# analog_channel_ABS_AMP.net
KiCad netlist of a schematic drawn in Altium Designer
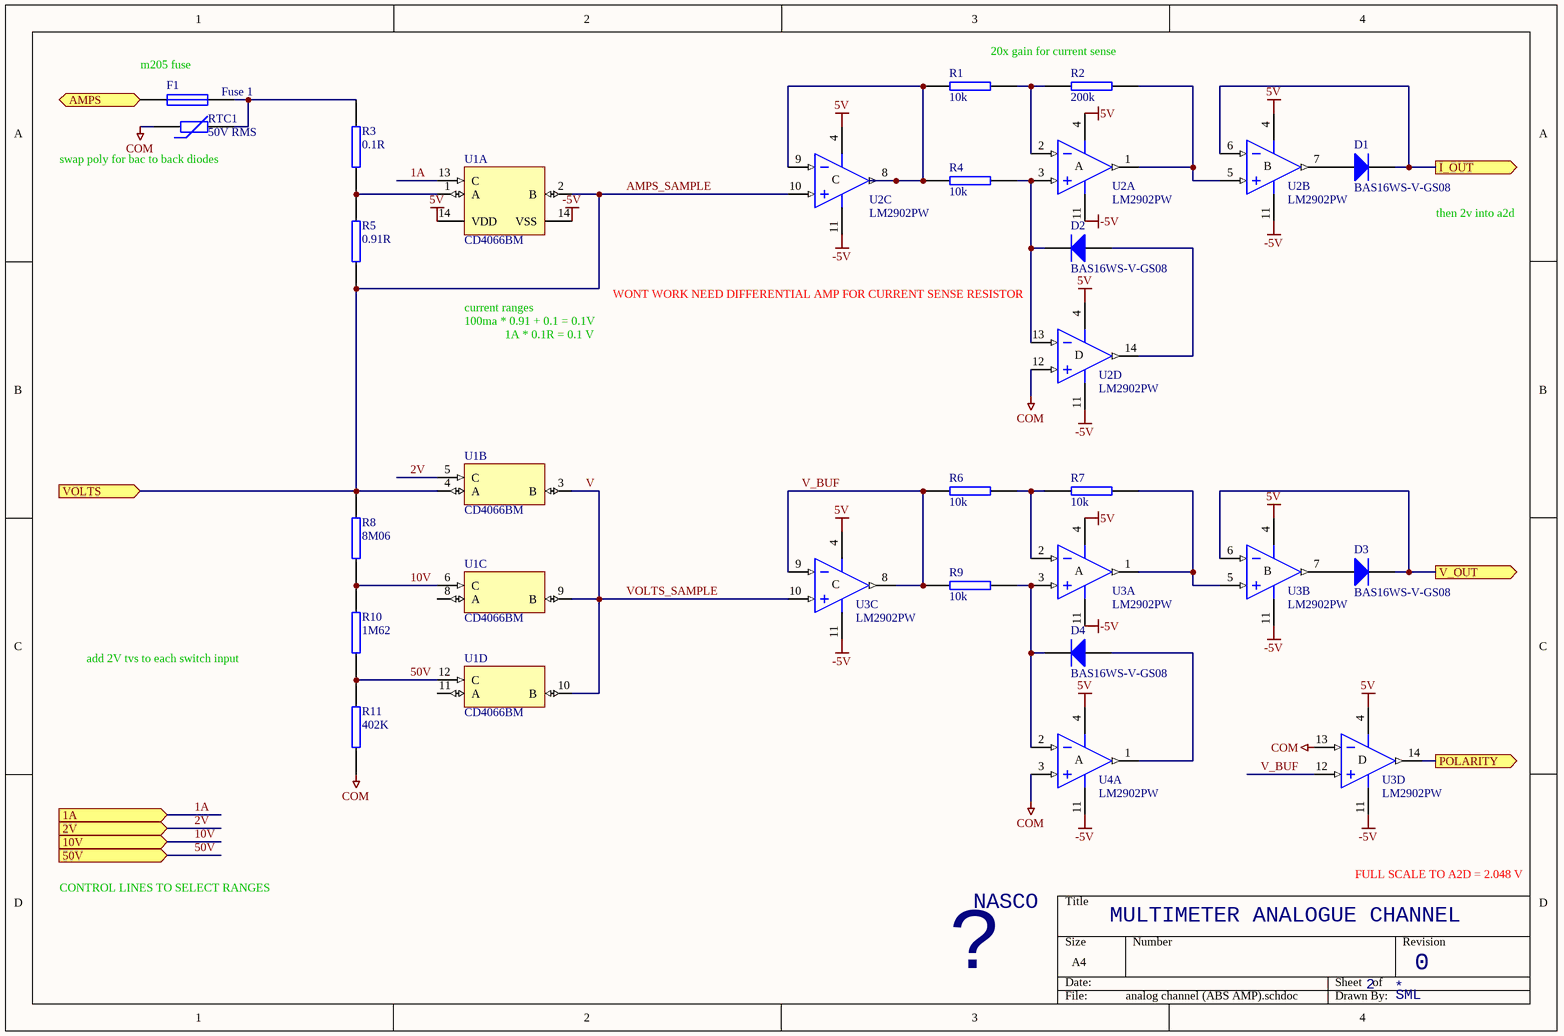
[diagram p0: analog channel (ABS AMP).schdoc]

(export (version "E")
  (design (tool "Eeschema 10.0.6"))
  (components
    (comp (ref "D1")
      (value "BAS16WS-V-GS08")
      (footprint "SMC")
      (description "Default Diode")
      (libsource (lib "Miscellaneous Devices") (part "Diode"))
    )
    (comp (ref "D2")
      (value "BAS16WS-V-GS08")
      (footprint "SMC")
      (description "Default Diode")
      (libsource (lib "Miscellaneous Devices") (part "Diode"))
    )
    (comp (ref "D3")
      (value "BAS16WS-V-GS08")
      (footprint "SMC")
      (description "Default Diode")
      (libsource (lib "Miscellaneous Devices") (part "Diode"))
    )
    (comp (ref "D4")
      (value "BAS16WS-V-GS08")
      (footprint "SMC")
      (description "Default Diode")
      (libsource (lib "Miscellaneous Devices") (part "Diode"))
    )
    (comp (ref "F1")
      (value "Fuse 1")
      (footprint "PIN-W2/E2.8")
      (description "Fuse")
      (libsource (lib "Miscellaneous Devices") (part "Fuse 1"))
    )
    (comp (ref "R1")
      (value "10k")
      (footprint "RES(3D) - 0603")
      (description "RESISTOR SMD 0603 10k")
      (fields (field (name "MOUSER PART NO.") "652-CR0603FX-1002ELF") (field (name "MANUFACTURER") "Bourns"))
      (libsource (lib "NASCO Resistors") (part "RES SMD 0603 10k"))
    )
    (comp (ref "R2")
      (value "200k")
      (footprint "RES(3D) - 0603")
      (description "RESISTOR SMD 0603 10k")
      (fields (field (name "MOUSER PART NO.") "652-CR0603FX-1002ELF") (field (name "MANUFACTURER") "Bourns"))
      (libsource (lib "NASCO Resistors") (part "RES SMD 0603 10k"))
    )
    (comp (ref "R3")
      (value "0.1R")
      (footprint "RES (3D) - 0805")
      (description "RESISTOR SMD 0603 10k")
      (fields (field (name "MOUSER PART NO.") "652-CRL0805JWR100ELF") (field (name "MANUFACTURER") "Bourns"))
      (libsource (lib "NASCO Resistors") (part "RES SMD 0603 10k"))
    )
    (comp (ref "R4")
      (value "10k")
      (footprint "RES(3D) - 0603")
      (description "RESISTOR SMD 0603 10k")
      (fields (field (name "MOUSER PART NO.") "652-CR0603FX-1002ELF") (field (name "MANUFACTURER") "Bourns"))
      (libsource (lib "NASCO Resistors") (part "RES SMD 0603 10k"))
    )
    (comp (ref "R5")
      (value "0.91R")
      (footprint "RES (3D) - 0805")
      (description "RESISTOR SMD 0603 10k")
      (fields (field (name "MOUSER PART NO.") "774-73L3R91J") (field (name "MANUFACTURER") "Bourns"))
      (libsource (lib "NASCO Resistors") (part "RES SMD 0603 10k"))
    )
    (comp (ref "R6")
      (value "10k")
      (footprint "RES(3D) - 0603")
      (description "RESISTOR SMD 0603 10k")
      (fields (field (name "MOUSER PART NO.") "652-CR0603FX-1002ELF") (field (name "MANUFACTURER") "Bourns"))
      (libsource (lib "NASCO Resistors") (part "RES SMD 0603 10k"))
    )
    (comp (ref "R7")
      (value "10k")
      (footprint "RES(3D) - 0603")
      (description "RESISTOR SMD 0603 10k")
      (fields (field (name "MOUSER PART NO.") "652-CR0603FX-1002ELF") (field (name "MANUFACTURER") "Bourns"))
      (libsource (lib "NASCO Resistors") (part "RES SMD 0603 10k"))
    )
    (comp (ref "R8")
      (value "8M06")
      (footprint "RES(3D) - 0603")
      (description "RESISTOR SMD 0603 10k")
      (fields
        (field (name "MOUSER PART NO.") "71-CRCW0603-8.06M-E3")
        (field (name "MANUFACTURER") "Vishay/Dale")
      )
      (libsource (lib "NASCO Resistors") (part "RES SMD 0603 10k"))
    )
    (comp (ref "R9")
      (value "10k")
      (footprint "RES(3D) - 0603")
      (description "RESISTOR SMD 0603 10k")
      (fields (field (name "MOUSER PART NO.") "652-CR0603FX-1002ELF") (field (name "MANUFACTURER") "Bourns"))
      (libsource (lib "NASCO Resistors") (part "RES SMD 0603 10k"))
    )
    (comp (ref "R10")
      (value "1M62")
      (footprint "RES(3D) - 0603")
      (description "RESISTOR SMD 0603 10k")
      (fields
        (field (name "MOUSER PART NO.") "Vishay/Dale")
        (field (name "MANUFACTURER") "71-CRCW0603-1.62M-E3")
      )
      (libsource (lib "NASCO Resistors") (part "RES SMD 0603 10k"))
    )
    (comp (ref "R11")
      (value "402K")
      (footprint "RES(3D) - 0603")
      (description "RESISTOR SMD 0603 10k")
      (fields (field (name "MOUSER PART NO.") "652-CR0603FX-4023ELF") (field (name "MANUFACTURER") "Bourns"))
      (libsource (lib "NASCO Resistors") (part "RES SMD 0603 10k"))
    )
    (comp (ref "RTC1")
      (value "50V RMS")
      (footprint "6-0805_N")
      (description "Varistor (Voltage-Sensitive Resistor)")
      (fields (field (name "MANUFACTURER") "Bourns") (field (name "MANUFACTURER PART NO.") "MOV-07D820K"))
      (libsource (lib "Miscellaneous Devices") (part "Res Varistor"))
    )
    (comp (ref "U1")
      (value "CD4066BM")
      (footprint "D014_N")
      (description "Quadruple Bilateral Analog Switch")
      (fields (field (name "MOUSER PART NUMBER") "595-CD4066BM"))
      (libsource (lib "Schlib1") (part "CD4066"))
    )
    (comp (ref "U2")
      (value "LM2902PW")
      (footprint "PW014_N")
      (description "Quadruple Operational Amplifier")
      (libsource (lib "TI Operational Amplifier") (part "LM2902PW"))
    )
    (comp (ref "U3")
      (value "LM2902PW")
      (footprint "PW014_N")
      (description "Quadruple Operational Amplifier")
      (libsource (lib "TI Operational Amplifier") (part "LM2902PW"))
    )
    (comp (ref "U4")
      (value "LM2902PW")
      (footprint "PW014_N")
      (description "Quadruple Operational Amplifier")
      (libsource (lib "TI Operational Amplifier") (part "LM2902PW"))
    )
  )
  (nets
    (net (code "1") (name "-5V") (class "Default")
      (node (ref "U1") (pin "14") (pinfunction "VSS_14") (pintype "passive"))
      (node (ref "U2") (pin "11") (pinfunction "V-_11") (pintype "power_in"))
      (node (ref "U3") (pin "11") (pinfunction "V-_11") (pintype "power_in"))
      (node (ref "U4") (pin "11") (pinfunction "V-_11") (pintype "power_in"))
    )
    (net (code "2") (name "/1A") (class "Default")
      (node (ref "U1") (pin "13") (pinfunction "C_13") (pintype "input"))
    )
    (net (code "3") (name "/2V") (class "Default")
      (node (ref "U1") (pin "5") (pinfunction "C_5") (pintype "input"))
    )
    (net (code "4") (name "/10V") (class "Default")
      (node (ref "R10") (pin "1") (pinfunction "1_1") (pintype "passive"))
      (node (ref "R8") (pin "2") (pinfunction "2_2") (pintype "passive"))
      (node (ref "U1") (pin "6") (pinfunction "C_6") (pintype "input"))
    )
    (net (code "5") (name "/50V") (class "Default")
      (node (ref "R10") (pin "2") (pinfunction "2_2") (pintype "passive"))
      (node (ref "R11") (pin "1") (pinfunction "1_1") (pintype "passive"))
      (node (ref "U1") (pin "12") (pinfunction "C_12") (pintype "input"))
    )
    (net (code "6") (name "/AMPS") (class "Default")
      (node (ref "F1") (pin "1") (pinfunction "1_1") (pintype "passive"))
    )
    (net (code "7") (name "/AMPS_SAMPLE") (class "Default")
      (node (ref "R5") (pin "2") (pinfunction "2_2") (pintype "passive"))
      (node (ref "R8") (pin "1") (pinfunction "1_1") (pintype "passive"))
      (node (ref "U1") (pin "2") (pinfunction "B_2") (pintype "bidirectional"))
      (node (ref "U1") (pin "4") (pinfunction "A_4") (pintype "bidirectional"))
      (node (ref "U2") (pin "10") (pinfunction "IN+_10") (pintype "input"))
    )
    (net (code "8") (name "/I_OUT") (class "Default")
      (node (ref "D1") (pin "2") (pinfunction "K_2") (pintype "passive"))
      (node (ref "U2") (pin "6") (pinfunction "IN-_6") (pintype "input"))
    )
    (net (code "9") (name "/POLARITY") (class "Default")
      (node (ref "U3") (pin "14") (pinfunction "OUT_14") (pintype "output"))
    )
    (net (code "10") (name "/V") (class "Default")
      (node (ref "U1") (pin "10") (pinfunction "B_10") (pintype "bidirectional"))
      (node (ref "U1") (pin "3") (pinfunction "B_3") (pintype "bidirectional"))
      (node (ref "U1") (pin "9") (pinfunction "B_9") (pintype "bidirectional"))
      (node (ref "U3") (pin "10") (pinfunction "IN+_10") (pintype "input"))
    )
    (net (code "11") (name "/V_BUF") (class "Default")
      (node (ref "R6") (pin "1") (pinfunction "1_1") (pintype "passive"))
      (node (ref "R9") (pin "1") (pinfunction "1_1") (pintype "passive"))
      (node (ref "U3") (pin "12") (pinfunction "IN+_12") (pintype "input"))
      (node (ref "U3") (pin "8") (pinfunction "OUT_8") (pintype "output"))
      (node (ref "U3") (pin "9") (pinfunction "IN-_9") (pintype "input"))
    )
    (net (code "12") (name "/V_OUT") (class "Default")
      (node (ref "D3") (pin "2") (pinfunction "K_2") (pintype "passive"))
      (node (ref "U3") (pin "6") (pinfunction "IN-_6") (pintype "input"))
    )
    (net (code "13") (name "5V") (class "Default")
      (node (ref "U1") (pin "14") (pinfunction "VDD_14") (pintype "passive"))
      (node (ref "U2") (pin "4") (pinfunction "V+_4") (pintype "power_in"))
      (node (ref "U3") (pin "4") (pinfunction "V+_4") (pintype "power_in"))
      (node (ref "U4") (pin "4") (pinfunction "V+_4") (pintype "power_in"))
    )
    (net (code "14") (name "COM") (class "Default")
      (node (ref "R11") (pin "2") (pinfunction "2_2") (pintype "passive"))
      (node (ref "RTC1") (pin "1") (pinfunction "1_1") (pintype "passive"))
      (node (ref "U2") (pin "12") (pinfunction "IN+_12") (pintype "input"))
      (node (ref "U3") (pin "13") (pinfunction "IN-_13") (pintype "input"))
      (node (ref "U4") (pin "3") (pinfunction "IN+_3") (pintype "input"))
    )
    (net (code "15") (name "Net-(D1-A)") (class "Default")
      (node (ref "D1") (pin "1") (pinfunction "A_1") (pintype "passive"))
      (node (ref "U2") (pin "7") (pinfunction "OUT_7") (pintype "output"))
    )
    (net (code "16") (name "Net-(D2-A)") (class "Default")
      (node (ref "D2") (pin "1") (pinfunction "A_1") (pintype "passive"))
      (node (ref "U2") (pin "14") (pinfunction "OUT_14") (pintype "output"))
    )
    (net (code "17") (name "Net-(D2-K)") (class "Default")
      (node (ref "D2") (pin "2") (pinfunction "K_2") (pintype "passive"))
      (node (ref "R4") (pin "2") (pinfunction "2_2") (pintype "passive"))
      (node (ref "U2") (pin "13") (pinfunction "IN-_13") (pintype "input"))
      (node (ref "U2") (pin "3") (pinfunction "IN+_3") (pintype "input"))
    )
    (net (code "18") (name "Net-(D3-A)") (class "Default")
      (node (ref "D3") (pin "1") (pinfunction "A_1") (pintype "passive"))
      (node (ref "U3") (pin "7") (pinfunction "OUT_7") (pintype "output"))
    )
    (net (code "19") (name "Net-(D4-A)") (class "Default")
      (node (ref "D4") (pin "1") (pinfunction "A_1") (pintype "passive"))
      (node (ref "U4") (pin "1") (pinfunction "OUT_1") (pintype "output"))
    )
    (net (code "20") (name "Net-(D4-K)") (class "Default")
      (node (ref "D4") (pin "2") (pinfunction "K_2") (pintype "passive"))
      (node (ref "R9") (pin "2") (pinfunction "2_2") (pintype "passive"))
      (node (ref "U3") (pin "3") (pinfunction "IN+_3") (pintype "input"))
      (node (ref "U4") (pin "2") (pinfunction "IN-_2") (pintype "input"))
    )
    (net (code "21") (name "Net-(F1-Pad2)") (class "Default")
      (node (ref "F1") (pin "2") (pinfunction "2_2") (pintype "passive"))
      (node (ref "R3") (pin "1") (pinfunction "1_1") (pintype "passive"))
      (node (ref "RTC1") (pin "2") (pinfunction "2_2") (pintype "passive"))
    )
    (net (code "22") (name "Net-(U1A-A)") (class "Default")
      (node (ref "R3") (pin "2") (pinfunction "2_2") (pintype "passive"))
      (node (ref "R5") (pin "1") (pinfunction "1_1") (pintype "passive"))
      (node (ref "U1") (pin "1") (pinfunction "A_1") (pintype "bidirectional"))
    )
    (net (code "23") (name "Net-(U2A-IN-)") (class "Default")
      (node (ref "R1") (pin "2") (pinfunction "2_2") (pintype "passive"))
      (node (ref "R2") (pin "1") (pinfunction "1_1") (pintype "passive"))
      (node (ref "U2") (pin "2") (pinfunction "IN-_2") (pintype "input"))
    )
    (net (code "24") (name "Net-(U2A-OUT)") (class "Default")
      (node (ref "R2") (pin "2") (pinfunction "2_2") (pintype "passive"))
      (node (ref "U2") (pin "1") (pinfunction "OUT_1") (pintype "output"))
      (node (ref "U2") (pin "5") (pinfunction "IN+_5") (pintype "input"))
    )
    (net (code "25") (name "Net-(U2C-IN-)") (class "Default")
      (node (ref "R1") (pin "1") (pinfunction "1_1") (pintype "passive"))
      (node (ref "R4") (pin "1") (pinfunction "1_1") (pintype "passive"))
      (node (ref "U2") (pin "8") (pinfunction "OUT_8") (pintype "output"))
      (node (ref "U2") (pin "9") (pinfunction "IN-_9") (pintype "input"))
    )
    (net (code "26") (name "Net-(U3A-IN-)") (class "Default")
      (node (ref "R6") (pin "2") (pinfunction "2_2") (pintype "passive"))
      (node (ref "R7") (pin "1") (pinfunction "1_1") (pintype "passive"))
      (node (ref "U3") (pin "2") (pinfunction "IN-_2") (pintype "input"))
    )
    (net (code "27") (name "Net-(U3A-OUT)") (class "Default")
      (node (ref "R7") (pin "2") (pinfunction "2_2") (pintype "passive"))
      (node (ref "U3") (pin "1") (pinfunction "OUT_1") (pintype "output"))
      (node (ref "U3") (pin "5") (pinfunction "IN+_5") (pintype "input"))
    )
    (net (code "28") (name "unconnected-(U1C-A-Pad8)") (class "Default")
      (node (ref "U1") (pin "8") (pinfunction "A_8") (pintype "bidirectional"))
    )
    (net (code "29") (name "unconnected-(U1D-A-Pad11)") (class "Default")
      (node (ref "U1") (pin "11") (pinfunction "A_11") (pintype "bidirectional"))
    )
  )
)
